# SQR_FG.net
KiCad netlist of a schematic drawn in EAGLE
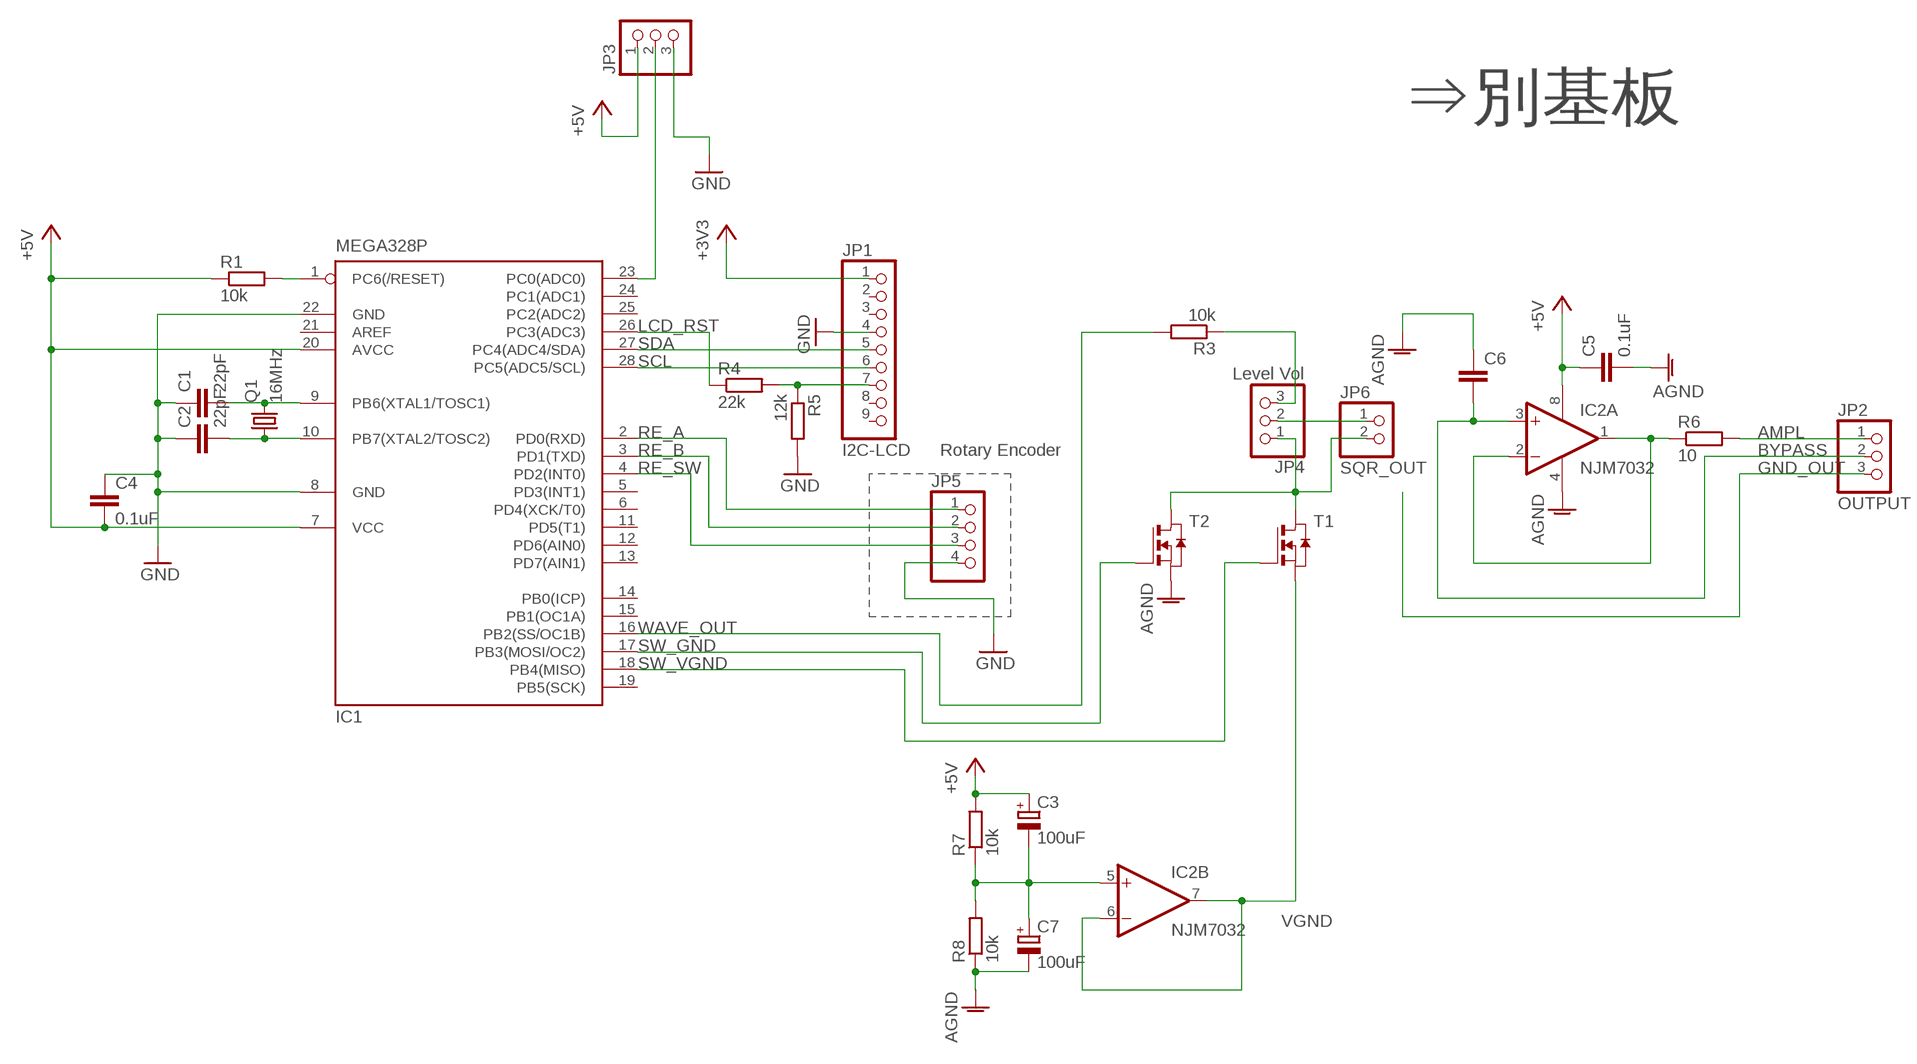
[diagram p0: schematic, sheet 1]

(export (version "E")
  (design (tool "Eeschema 10.0.6"))
  (components
    (comp (ref "C1")
      (value "22pF")
      (footprint "eagle-import:C025-024X044")
      (libsource (lib "eagle-import") (part "C-EU025-024X044"))
    )
    (comp (ref "C2")
      (value "22pF")
      (footprint "eagle-import:C025-024X044")
      (libsource (lib "eagle-import") (part "C-EU025-024X044"))
    )
    (comp (ref "C3")
      (value "100uF")
      (footprint "eagle-import:E2,5-5")
      (libsource (lib "eagle-import") (part "CPOL-EUE2.5-5"))
    )
    (comp (ref "C4")
      (value "0.1uF")
      (footprint "eagle-import:C025-024X044")
      (libsource (lib "eagle-import") (part "C-EU025-024X044"))
    )
    (comp (ref "C5")
      (value "0.1uF")
      (footprint "eagle-import:C025-024X044")
      (libsource (lib "eagle-import") (part "C-EU025-024X044"))
    )
    (comp (ref "C6")
      (value "C-EU025-024X044")
      (footprint "eagle-import:C025-024X044")
      (libsource (lib "eagle-import") (part "C-EU025-024X044"))
    )
    (comp (ref "C7")
      (value "100uF")
      (footprint "eagle-import:E2,5-5")
      (libsource (lib "eagle-import") (part "CPOL-EUE2.5-5"))
    )
    (comp (ref "IC1")
      (value "MEGA328P")
      (footprint "eagle-import:DIL28-3")
      (libsource (lib "eagle-import") (part "MEGA8-P"))
    )
    (comp (ref "IC2")
      (value "NJM7032")
      (footprint "eagle-import:DIL08")
      (libsource (lib "eagle-import") (part "LM358N"))
    )
    (comp (ref "JP1")
      (value "I2C-LCD")
      (footprint "eagle-import:1X09")
      (libsource (lib "eagle-import") (part "PINHD-1X9"))
    )
    (comp (ref "JP2")
      (value "OUTPUT")
      (footprint "eagle-import:1X03")
      (libsource (lib "eagle-import") (part "PINHD-1X3"))
    )
    (comp (ref "JP3")
      (value "PINHD-1X3")
      (footprint "eagle-import:1X03")
      (libsource (lib "eagle-import") (part "PINHD-1X3"))
    )
    (comp (ref "JP4")
      (value "Level Vol")
      (footprint "eagle-import:1X03")
      (libsource (lib "eagle-import") (part "PINHD-1X3"))
    )
    (comp (ref "JP5")
      (value "PINHD-1X4")
      (footprint "eagle-import:1X04")
      (libsource (lib "eagle-import") (part "PINHD-1X4"))
    )
    (comp (ref "JP6")
      (value "SQR_OUT")
      (footprint "eagle-import:1X02")
      (libsource (lib "eagle-import") (part "PINHD-1X2"))
    )
    (comp (ref "Q1")
      (value "16MHz")
      (footprint "eagle-import:HC49_S")
      (libsource (lib "eagle-import") (part "CRYSTALHC49S"))
    )
    (comp (ref "R1")
      (value "10k")
      (footprint "eagle-import:0207_7")
      (libsource (lib "eagle-import") (part "R-EU_0207/7"))
    )
    (comp (ref "R3")
      (value "10k")
      (footprint "eagle-import:0207_7")
      (libsource (lib "eagle-import") (part "R-EU_0207/7"))
    )
    (comp (ref "R4")
      (value "22k")
      (footprint "eagle-import:0207_7")
      (libsource (lib "eagle-import") (part "R-EU_0207/7"))
    )
    (comp (ref "R5")
      (value "12k")
      (footprint "eagle-import:0207_7")
      (libsource (lib "eagle-import") (part "R-EU_0207/7"))
    )
    (comp (ref "R6")
      (value "10")
      (footprint "eagle-import:0207_7")
      (libsource (lib "eagle-import") (part "R-EU_0207/7"))
    )
    (comp (ref "R7")
      (value "10k")
      (footprint "eagle-import:0207_7")
      (libsource (lib "eagle-import") (part "R-EU_0207/7"))
    )
    (comp (ref "R8")
      (value "10k")
      (footprint "eagle-import:0207_7")
      (libsource (lib "eagle-import") (part "R-EU_0207/7"))
    )
    (comp (ref "T1")
      (value "NMOSE3L")
      (footprint "eagle-import:E3LINE")
      (libsource (lib "eagle-import") (part "NMOSE3L"))
    )
    (comp (ref "T2")
      (value "NMOSE3L")
      (footprint "eagle-import:E3LINE")
      (libsource (lib "eagle-import") (part "NMOSE3L"))
    )
  )
  (nets
    (net (code "1") (name "+3V3") (class "Default")
      (node (ref "JP1") (pin "1") (pinfunction "1_1") (pintype "passive"))
    )
    (net (code "2") (name "+5V") (class "Default")
      (node (ref "C3") (pin "+") (pinfunction "+_+") (pintype "passive"))
      (node (ref "C4") (pin "2") (pinfunction "2_2") (pintype "passive"))
      (node (ref "C5") (pin "1") (pinfunction "1_1") (pintype "passive"))
      (node (ref "IC1") (pin "20") (pinfunction "AVCC_20") (pintype "power_in"))
      (node (ref "IC1") (pin "7") (pinfunction "VCC_7") (pintype "power_in"))
      (node (ref "IC2") (pin "8") (pinfunction "V+_8") (pintype "power_in"))
      (node (ref "JP3") (pin "1") (pinfunction "1_1") (pintype "passive"))
      (node (ref "R1") (pin "1") (pinfunction "1_1") (pintype "passive"))
      (node (ref "R7") (pin "2") (pinfunction "2_2") (pintype "passive"))
    )
    (net (code "3") (name "/AMPL") (class "Default")
      (node (ref "JP2") (pin "1") (pinfunction "1_1") (pintype "passive"))
      (node (ref "R6") (pin "2") (pinfunction "2_2") (pintype "passive"))
    )
    (net (code "4") (name "/BYPASS") (class "Default")
      (node (ref "C6") (pin "2") (pinfunction "2_2") (pintype "passive"))
      (node (ref "IC2") (pin "3") (pinfunction "+IN_3") (pintype "input"))
      (node (ref "JP2") (pin "2") (pinfunction "2_2") (pintype "passive"))
    )
    (net (code "5") (name "/GND_OUT") (class "Default")
      (node (ref "JP2") (pin "3") (pinfunction "3_3") (pintype "passive"))
    )
    (net (code "6") (name "/LCD_RST") (class "Default")
      (node (ref "IC1") (pin "26") (pinfunction "PC3(ADC3)_26") (pintype "bidirectional"))
      (node (ref "R4") (pin "1") (pinfunction "1_1") (pintype "passive"))
    )
    (net (code "7") (name "/RE_A") (class "Default")
      (node (ref "IC1") (pin "2") (pinfunction "PD0(RXD)_2") (pintype "bidirectional"))
      (node (ref "JP5") (pin "1") (pinfunction "1_1") (pintype "passive"))
    )
    (net (code "8") (name "/RE_B") (class "Default")
      (node (ref "IC1") (pin "3") (pinfunction "PD1(TXD)_3") (pintype "bidirectional"))
      (node (ref "JP5") (pin "2") (pinfunction "2_2") (pintype "passive"))
    )
    (net (code "9") (name "/RE_SW") (class "Default")
      (node (ref "IC1") (pin "4") (pinfunction "PD2(INT0)_4") (pintype "bidirectional"))
      (node (ref "JP5") (pin "3") (pinfunction "3_3") (pintype "passive"))
    )
    (net (code "10") (name "/SCL") (class "Default")
      (node (ref "IC1") (pin "28") (pinfunction "PC5(ADC5/SCL)_28") (pintype "bidirectional"))
      (node (ref "JP1") (pin "6") (pinfunction "6_6") (pintype "passive"))
    )
    (net (code "11") (name "/SDA") (class "Default")
      (node (ref "IC1") (pin "27") (pinfunction "PC4(ADC4/SDA)_27") (pintype "bidirectional"))
      (node (ref "JP1") (pin "5") (pinfunction "5_5") (pintype "passive"))
    )
    (net (code "12") (name "/SW_GND") (class "Default")
      (node (ref "IC1") (pin "17") (pinfunction "PB3(MOSI/OC2)_17") (pintype "bidirectional"))
      (node (ref "T2") (pin "2") (pinfunction "G_2") (pintype "passive"))
    )
    (net (code "13") (name "/SW_VGND") (class "Default")
      (node (ref "IC1") (pin "18") (pinfunction "PB4(MISO)_18") (pintype "bidirectional"))
      (node (ref "T1") (pin "2") (pinfunction "G_2") (pintype "passive"))
    )
    (net (code "14") (name "/VGND") (class "Default")
      (node (ref "IC2") (pin "6") (pinfunction "-IN_6") (pintype "input"))
      (node (ref "IC2") (pin "7") (pinfunction "OUT_7") (pintype "output"))
      (node (ref "T1") (pin "3") (pinfunction "S_3") (pintype "passive"))
    )
    (net (code "15") (name "/WAVE_OUT") (class "Default")
      (node (ref "IC1") (pin "16") (pinfunction "PB2(SS/OC1B)_16") (pintype "bidirectional"))
      (node (ref "R3") (pin "2") (pinfunction "2_2") (pintype "passive"))
    )
    (net (code "16") (name "AGND") (class "Default")
      (node (ref "C5") (pin "2") (pinfunction "2_2") (pintype "passive"))
      (node (ref "C6") (pin "1") (pinfunction "1_1") (pintype "passive"))
      (node (ref "C7") (pin "-") (pinfunction "-_-") (pintype "passive"))
      (node (ref "IC2") (pin "4") (pinfunction "V-_4") (pintype "power_in"))
      (node (ref "R8") (pin "1") (pinfunction "1_1") (pintype "passive"))
      (node (ref "T2") (pin "3") (pinfunction "S_3") (pintype "passive"))
    )
    (net (code "17") (name "GND") (class "Default")
      (node (ref "C1") (pin "1") (pinfunction "1_1") (pintype "passive"))
      (node (ref "C2") (pin "1") (pinfunction "1_1") (pintype "passive"))
      (node (ref "C4") (pin "1") (pinfunction "1_1") (pintype "passive"))
      (node (ref "IC1") (pin "22") (pinfunction "GND_22") (pintype "power_in"))
      (node (ref "IC1") (pin "8") (pinfunction "GND_8") (pintype "power_in"))
      (node (ref "JP1") (pin "4") (pinfunction "4_4") (pintype "passive"))
      (node (ref "JP3") (pin "3") (pinfunction "3_3") (pintype "passive"))
      (node (ref "JP5") (pin "4") (pinfunction "4_4") (pintype "passive"))
      (node (ref "R5") (pin "2") (pinfunction "2_2") (pintype "passive"))
    )
    (net (code "18") (name "Net-(IC1-PB6(XTAL1{slash}TOSC1))") (class "Default")
      (node (ref "C1") (pin "2") (pinfunction "2_2") (pintype "passive"))
      (node (ref "IC1") (pin "9") (pinfunction "PB6(XTAL1/TOSC1)_9") (pintype "bidirectional"))
      (node (ref "Q1") (pin "2") (pinfunction "2_2") (pintype "passive"))
    )
    (net (code "19") (name "Net-(IC1-PB7(XTAL2{slash}TOSC2))") (class "Default")
      (node (ref "C2") (pin "2") (pinfunction "2_2") (pintype "passive"))
      (node (ref "IC1") (pin "10") (pinfunction "PB7(XTAL2/TOSC2)_10") (pintype "bidirectional"))
      (node (ref "Q1") (pin "1") (pinfunction "1_1") (pintype "passive"))
    )
    (net (code "20") (name "Net-(IC1-PC0(ADC0))") (class "Default")
      (node (ref "IC1") (pin "23") (pinfunction "PC0(ADC0)_23") (pintype "bidirectional"))
      (node (ref "JP3") (pin "2") (pinfunction "2_2") (pintype "passive"))
    )
    (net (code "21") (name "Net-(IC1-PC6({slash}RESET))") (class "Default")
      (node (ref "IC1") (pin "1") (pinfunction "PC6(/RESET)_1") (pintype "bidirectional"))
      (node (ref "R1") (pin "2") (pinfunction "2_2") (pintype "passive"))
    )
    (net (code "22") (name "Net-(IC2A--IN)") (class "Default")
      (node (ref "IC2") (pin "1") (pinfunction "OUT_1") (pintype "output"))
      (node (ref "IC2") (pin "2") (pinfunction "-IN_2") (pintype "input"))
      (node (ref "R6") (pin "1") (pinfunction "1_1") (pintype "passive"))
    )
    (net (code "23") (name "Net-(IC2B-+IN)") (class "Default")
      (node (ref "C3") (pin "-") (pinfunction "-_-") (pintype "passive"))
      (node (ref "C7") (pin "+") (pinfunction "+_+") (pintype "passive"))
      (node (ref "IC2") (pin "5") (pinfunction "+IN_5") (pintype "input"))
      (node (ref "R7") (pin "1") (pinfunction "1_1") (pintype "passive"))
      (node (ref "R8") (pin "2") (pinfunction "2_2") (pintype "passive"))
    )
    (net (code "24") (name "Net-(JP1-Pad7)") (class "Default")
      (node (ref "JP1") (pin "7") (pinfunction "7_7") (pintype "passive"))
      (node (ref "R4") (pin "2") (pinfunction "2_2") (pintype "passive"))
      (node (ref "R5") (pin "1") (pinfunction "1_1") (pintype "passive"))
    )
    (net (code "25") (name "Net-(JP4-Pad2)") (class "Default")
      (node (ref "JP4") (pin "2") (pinfunction "2_2") (pintype "passive"))
      (node (ref "JP6") (pin "1") (pinfunction "1_1") (pintype "passive"))
    )
    (net (code "26") (name "Net-(JP4-Pad3)") (class "Default")
      (node (ref "JP4") (pin "3") (pinfunction "3_3") (pintype "passive"))
      (node (ref "R3") (pin "1") (pinfunction "1_1") (pintype "passive"))
    )
    (net (code "27") (name "Net-(T1-D)") (class "Default")
      (node (ref "JP4") (pin "1") (pinfunction "1_1") (pintype "passive"))
      (node (ref "JP6") (pin "2") (pinfunction "2_2") (pintype "passive"))
      (node (ref "T1") (pin "1") (pinfunction "D_1") (pintype "passive"))
      (node (ref "T2") (pin "1") (pinfunction "D_1") (pintype "passive"))
    )
    (net (code "28") (name "unconnected-(IC1-AREF-Pad21)") (class "Default")
      (node (ref "IC1") (pin "21") (pinfunction "AREF_21") (pintype "passive"))
    )
    (net (code "29") (name "unconnected-(IC1-PB0(ICP)-Pad14)") (class "Default")
      (node (ref "IC1") (pin "14") (pinfunction "PB0(ICP)_14") (pintype "bidirectional"))
    )
    (net (code "30") (name "unconnected-(IC1-PB1(OC1A)-Pad15)") (class "Default")
      (node (ref "IC1") (pin "15") (pinfunction "PB1(OC1A)_15") (pintype "bidirectional"))
    )
    (net (code "31") (name "unconnected-(IC1-PB5(SCK)-Pad19)") (class "Default")
      (node (ref "IC1") (pin "19") (pinfunction "PB5(SCK)_19") (pintype "bidirectional"))
    )
    (net (code "32") (name "unconnected-(IC1-PC1(ADC1)-Pad24)") (class "Default")
      (node (ref "IC1") (pin "24") (pinfunction "PC1(ADC1)_24") (pintype "bidirectional"))
    )
    (net (code "33") (name "unconnected-(IC1-PC2(ADC2)-Pad25)") (class "Default")
      (node (ref "IC1") (pin "25") (pinfunction "PC2(ADC2)_25") (pintype "bidirectional"))
    )
    (net (code "34") (name "unconnected-(IC1-PD3(INT1)-Pad5)") (class "Default")
      (node (ref "IC1") (pin "5") (pinfunction "PD3(INT1)_5") (pintype "bidirectional"))
    )
    (net (code "35") (name "unconnected-(IC1-PD4(XCK{slash}T0)-Pad6)") (class "Default")
      (node (ref "IC1") (pin "6") (pinfunction "PD4(XCK/T0)_6") (pintype "bidirectional"))
    )
    (net (code "36") (name "unconnected-(IC1-PD5(T1)-Pad11)") (class "Default")
      (node (ref "IC1") (pin "11") (pinfunction "PD5(T1)_11") (pintype "bidirectional"))
    )
    (net (code "37") (name "unconnected-(IC1-PD6(AIN0)-Pad12)") (class "Default")
      (node (ref "IC1") (pin "12") (pinfunction "PD6(AIN0)_12") (pintype "bidirectional"))
    )
    (net (code "38") (name "unconnected-(IC1-PD7(AIN1)-Pad13)") (class "Default")
      (node (ref "IC1") (pin "13") (pinfunction "PD7(AIN1)_13") (pintype "bidirectional"))
    )
    (net (code "39") (name "unconnected-(JP1-Pad2)") (class "Default")
      (node (ref "JP1") (pin "2") (pinfunction "2_2") (pintype "passive"))
    )
    (net (code "40") (name "unconnected-(JP1-Pad3)") (class "Default")
      (node (ref "JP1") (pin "3") (pinfunction "3_3") (pintype "passive"))
    )
    (net (code "41") (name "unconnected-(JP1-Pad8)") (class "Default")
      (node (ref "JP1") (pin "8") (pinfunction "8_8") (pintype "passive"))
    )
    (net (code "42") (name "unconnected-(JP1-Pad9)") (class "Default")
      (node (ref "JP1") (pin "9") (pinfunction "9_9") (pintype "passive"))
    )
  )
)
